# uzenet-module-v2_0.net
KiCad netlist of a schematic drawn in EAGLE
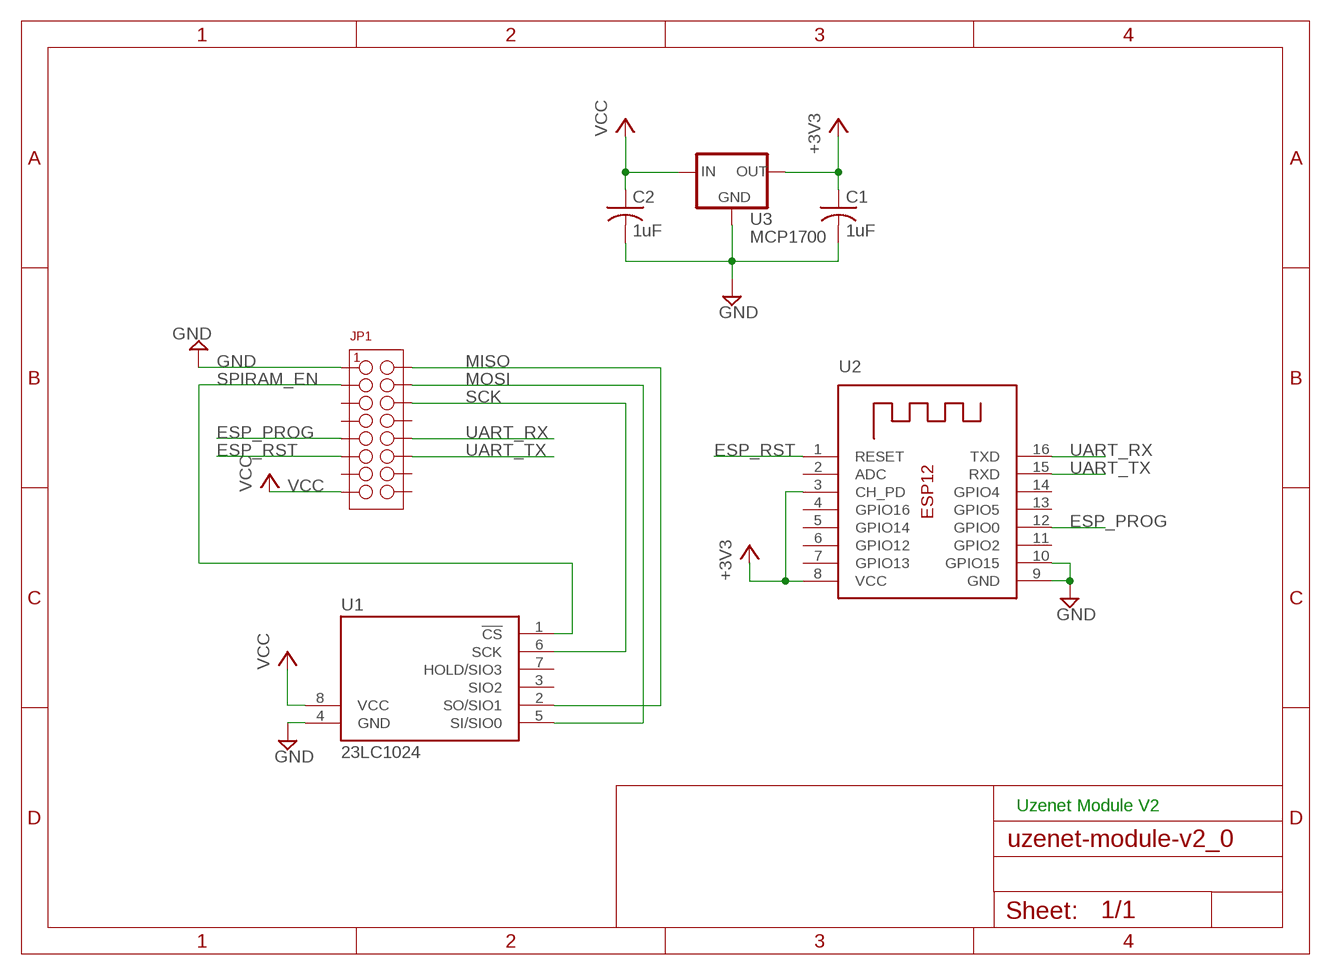
[diagram p0: schematic, sheet 1]

(export (version "E")
  (design (tool "Eeschema 10.0.6"))
  (components
    (comp (ref "C1")
      (value "1uF")
      (footprint "eagle-import:C025-025X050")
      (libsource (lib "eagle-import") (part "C-US025-025X050"))
    )
    (comp (ref "C2")
      (value "1uF")
      (footprint "eagle-import:C025-025X050")
      (libsource (lib "eagle-import") (part "C-US025-025X050"))
    )
    (comp (ref "JP1")
      (value "NPPC082KFMS-RC")
      (footprint "eagle-import:HEADER_2X8_SMT_BOTTOM_LAYER")
      (libsource (lib "eagle-import") (part "NPPC082KFMS-RC"))
    )
    (comp (ref "U1")
      (value "23LC1024")
      (footprint "eagle-import:DIL08")
      (libsource (lib "eagle-import") (part "23LC1024"))
    )
    (comp (ref "U2")
      (value "ESP-12")
      (footprint "eagle-import:ESP-12")
      (libsource (lib "eagle-import") (part "ESP-12"))
    )
    (comp (ref "U3")
      (value "MCP1700")
      (footprint "eagle-import:TO92-INLINE")
      (libsource (lib "eagle-import") (part "MCP1700INLINE"))
    )
  )
  (nets
    (net (code "1") (name "+3V3") (class "Default")
      (node (ref "C1") (pin "1") (pinfunction "1_1") (pintype "passive"))
      (node (ref "U2") (pin "3") (pinfunction "CH_PD_3") (pintype "input"))
      (node (ref "U2") (pin "8") (pinfunction "VCC_8") (pintype "power_in"))
      (node (ref "U3") (pin "3") (pinfunction "OUT_3") (pintype "passive"))
    )
    (net (code "2") (name "/ESP_PROG") (class "Default")
      (node (ref "JP1") (pin "P$9") (pinfunction "P$9_P$9") (pintype "bidirectional"))
      (node (ref "U2") (pin "12") (pinfunction "GPIO0_12") (pintype "bidirectional"))
    )
    (net (code "3") (name "/ESP_RST") (class "Default")
      (node (ref "JP1") (pin "P$11") (pinfunction "P$11_P$11") (pintype "bidirectional"))
      (node (ref "U2") (pin "1") (pinfunction "RESET_1") (pintype "input"))
    )
    (net (code "4") (name "/MISO") (class "Default")
      (node (ref "JP1") (pin "P$2") (pinfunction "P$2_P$2") (pintype "bidirectional"))
      (node (ref "U1") (pin "2") (pinfunction "SO/SIO1_2") (pintype "bidirectional"))
    )
    (net (code "5") (name "/MOSI") (class "Default")
      (node (ref "JP1") (pin "P$4") (pinfunction "P$4_P$4") (pintype "bidirectional"))
      (node (ref "U1") (pin "5") (pinfunction "SI/SIO0_5") (pintype "bidirectional"))
    )
    (net (code "6") (name "/SCK") (class "Default")
      (node (ref "JP1") (pin "P$6") (pinfunction "P$6_P$6") (pintype "bidirectional"))
      (node (ref "U1") (pin "6") (pinfunction "SCK_6") (pintype "input"))
    )
    (net (code "7") (name "/SPIRAM_EN") (class "Default")
      (node (ref "JP1") (pin "P$3") (pinfunction "P$3_P$3") (pintype "bidirectional"))
      (node (ref "U1") (pin "1") (pinfunction "~{CS}_1") (pintype "input"))
    )
    (net (code "8") (name "/UART_RX") (class "Default")
      (node (ref "JP1") (pin "P$10") (pinfunction "P$10_P$10") (pintype "bidirectional"))
      (node (ref "U2") (pin "16") (pinfunction "TXD_16") (pintype "output"))
    )
    (net (code "9") (name "/UART_TX") (class "Default")
      (node (ref "JP1") (pin "P$12") (pinfunction "P$12_P$12") (pintype "bidirectional"))
      (node (ref "U2") (pin "15") (pinfunction "RXD_15") (pintype "input"))
    )
    (net (code "10") (name "GND") (class "Default")
      (node (ref "C1") (pin "2") (pinfunction "2_2") (pintype "passive"))
      (node (ref "C2") (pin "2") (pinfunction "2_2") (pintype "passive"))
      (node (ref "JP1") (pin "P$1") (pinfunction "P$1_P$1") (pintype "bidirectional"))
      (node (ref "U1") (pin "4") (pinfunction "GND_4") (pintype "power_in"))
      (node (ref "U2") (pin "10") (pinfunction "GPIO15_10") (pintype "bidirectional"))
      (node (ref "U2") (pin "9") (pinfunction "GND_9") (pintype "power_in"))
      (node (ref "U3") (pin "1") (pinfunction "GND_1") (pintype "input"))
    )
    (net (code "11") (name "VCC") (class "Default")
      (node (ref "C2") (pin "1") (pinfunction "1_1") (pintype "passive"))
      (node (ref "JP1") (pin "P$15") (pinfunction "P$15_P$15") (pintype "bidirectional"))
      (node (ref "U1") (pin "8") (pinfunction "VCC_8") (pintype "power_in"))
      (node (ref "U3") (pin "2") (pinfunction "IN_2") (pintype "input"))
    )
    (net (code "12") (name "unconnected-(JP1-PadP$5)") (class "Default")
      (node (ref "JP1") (pin "P$5") (pinfunction "P$5_P$5") (pintype "bidirectional"))
    )
    (net (code "13") (name "unconnected-(JP1-PadP$7)") (class "Default")
      (node (ref "JP1") (pin "P$7") (pinfunction "P$7_P$7") (pintype "bidirectional"))
    )
    (net (code "14") (name "unconnected-(JP1-PadP$8)") (class "Default")
      (node (ref "JP1") (pin "P$8") (pinfunction "P$8_P$8") (pintype "bidirectional"))
    )
    (net (code "15") (name "unconnected-(JP1-PadP$13)") (class "Default")
      (node (ref "JP1") (pin "P$13") (pinfunction "P$13_P$13") (pintype "bidirectional"))
    )
    (net (code "16") (name "unconnected-(JP1-PadP$14)") (class "Default")
      (node (ref "JP1") (pin "P$14") (pinfunction "P$14_P$14") (pintype "bidirectional"))
    )
    (net (code "17") (name "unconnected-(JP1-PadP$16)") (class "Default")
      (node (ref "JP1") (pin "P$16") (pinfunction "P$16_P$16") (pintype "bidirectional"))
    )
    (net (code "18") (name "unconnected-(U1-HOLD{slash}SIO3-Pad7)") (class "Default")
      (node (ref "U1") (pin "7") (pinfunction "HOLD/SIO3_7") (pintype "bidirectional"))
    )
    (net (code "19") (name "unconnected-(U1-SIO2-Pad3)") (class "Default")
      (node (ref "U1") (pin "3") (pinfunction "SIO2_3") (pintype "bidirectional"))
    )
    (net (code "20") (name "unconnected-(U2-ADC-Pad2)") (class "Default")
      (node (ref "U2") (pin "2") (pinfunction "ADC_2") (pintype "passive"))
    )
    (net (code "21") (name "unconnected-(U2-GPIO2-Pad11)") (class "Default")
      (node (ref "U2") (pin "11") (pinfunction "GPIO2_11") (pintype "bidirectional"))
    )
    (net (code "22") (name "unconnected-(U2-GPIO4-Pad14)") (class "Default")
      (node (ref "U2") (pin "14") (pinfunction "GPIO4_14") (pintype "bidirectional"))
    )
    (net (code "23") (name "unconnected-(U2-GPIO5-Pad13)") (class "Default")
      (node (ref "U2") (pin "13") (pinfunction "GPIO5_13") (pintype "bidirectional"))
    )
    (net (code "24") (name "unconnected-(U2-GPIO12-Pad6)") (class "Default")
      (node (ref "U2") (pin "6") (pinfunction "GPIO12_6") (pintype "bidirectional"))
    )
    (net (code "25") (name "unconnected-(U2-GPIO13-Pad7)") (class "Default")
      (node (ref "U2") (pin "7") (pinfunction "GPIO13_7") (pintype "bidirectional"))
    )
    (net (code "26") (name "unconnected-(U2-GPIO14-Pad5)") (class "Default")
      (node (ref "U2") (pin "5") (pinfunction "GPIO14_5") (pintype "bidirectional"))
    )
    (net (code "27") (name "unconnected-(U2-GPIO16-Pad4)") (class "Default")
      (node (ref "U2") (pin "4") (pinfunction "GPIO16_4") (pintype "bidirectional"))
    )
  )
)
